# AUDIO_CODEC.net
KiCad netlist of a schematic drawn in Altium Designer
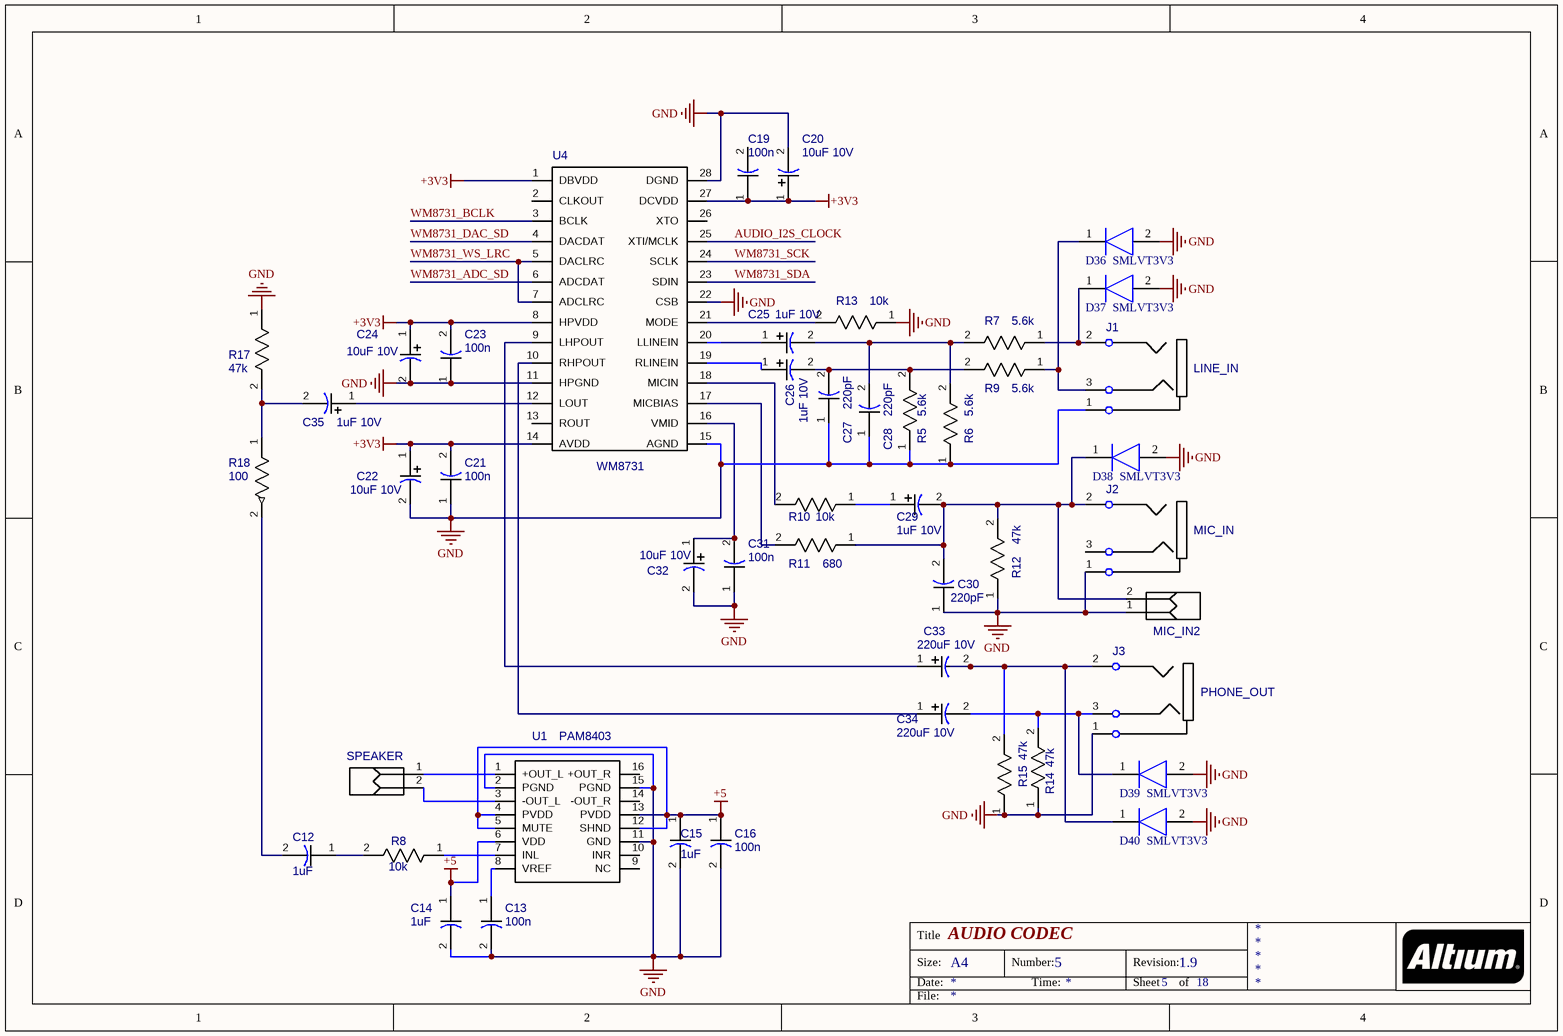
[diagram p0: AUDIO CODEC.SchDoc]

(export (version "E")
  (design (tool "Eeschema 10.0.6"))
  (components
    (comp (ref "C12")
      (value "1uF")
      (footprint "CAP_0805")
      (description "CAP_0805")
      (libsource (lib "*") (part "CAP_0805"))
    )
    (comp (ref "C13")
      (value "100n")
      (footprint "CAP_0805")
      (description "CAP_0805")
      (libsource (lib "*") (part "CAP_0805"))
    )
    (comp (ref "C14")
      (value "1uF")
      (footprint "CAP_0805")
      (description "CAP_0805")
      (libsource (lib "*") (part "CAP_0805"))
    )
    (comp (ref "C15")
      (value "1uF")
      (footprint "CAP_0805")
      (description "CAP_0805")
      (libsource (lib "*") (part "CAP_0805"))
    )
    (comp (ref "C16")
      (value "100n")
      (footprint "CAP_0805")
      (description "CAP_0805")
      (libsource (lib "*") (part "CAP_0805"))
    )
    (comp (ref "C19")
      (value "100n")
      (footprint "CAP_0805")
      (description "CAP_0805")
      (libsource (lib "*") (part "CAP_0805"))
    )
    (comp (ref "C20")
      (value "10uF 10V")
      (footprint "CAPAE_4.3x4.3h5.4")
      (description "CAPAE_4.3x4.3h5.4")
      (libsource (lib "*") (part "CAPAE_4.3x4.3h5.4"))
    )
    (comp (ref "C21")
      (value "100n")
      (footprint "CAP_0805")
      (description "CAP_0805")
      (libsource (lib "*") (part "CAP_0805"))
    )
    (comp (ref "C22")
      (value "10uF 10V")
      (footprint "CAPAE_4.3x4.3h5.4")
      (description "CAPAE_4.3x4.3h5.4")
      (libsource (lib "*") (part "CAPAE_4.3x4.3h5.4"))
    )
    (comp (ref "C23")
      (value "100n")
      (footprint "CAP_0805")
      (description "CAP_0805")
      (libsource (lib "*") (part "CAP_0805"))
    )
    (comp (ref "C24")
      (value "10uF 10V")
      (footprint "CAPAE_4.3x4.3h5.4")
      (description "CAPAE_4.3x4.3h5.4")
      (libsource (lib "*") (part "CAPAE_4.3x4.3h5.4"))
    )
    (comp (ref "C25")
      (value "1uF 10V")
      (footprint "CAPAE_4.3x4.3h5.4")
      (description "CAPAE_4.3x4.3h5.4")
      (libsource (lib "*") (part "CAPAE_4.3x4.3h5.4"))
    )
    (comp (ref "C26")
      (value "1uF 10V")
      (footprint "CAPAE_4.3x4.3h5.4")
      (description "CAPAE_4.3x4.3h5.4")
      (libsource (lib "*") (part "CAPAE_4.3x4.3h5.4"))
    )
    (comp (ref "C27")
      (value "220pF")
      (footprint "CAP_0805")
      (description "CAP_0805")
      (libsource (lib "*") (part "CAP_0805"))
    )
    (comp (ref "C28")
      (value "220pF")
      (footprint "CAP_0805")
      (description "CAP_0805")
      (libsource (lib "*") (part "CAP_0805"))
    )
    (comp (ref "C29")
      (value "1uF 10V")
      (footprint "CAPAE_4.3x4.3h5.4")
      (description "CAPAE_4.3x4.3h5.4")
      (libsource (lib "*") (part "CAPAE_4.3x4.3h5.4"))
    )
    (comp (ref "C30")
      (value "220pF")
      (footprint "CAP_0805")
      (description "CAP_0805")
      (libsource (lib "*") (part "CAP_0805"))
    )
    (comp (ref "C31")
      (value "100n")
      (footprint "CAP_0805")
      (description "CAP_0805")
      (libsource (lib "*") (part "CAP_0805"))
    )
    (comp (ref "C32")
      (value "10uF 10V")
      (footprint "CAPAE_4.3x4.3h5.4")
      (description "CAPAE_4.3x4.3h5.4")
      (libsource (lib "*") (part "CAPAE_4.3x4.3h5.4"))
    )
    (comp (ref "C33")
      (value "220uF 10V")
      (footprint "CAPAE_4.3x4.3h5.4")
      (description "CAPAE_4.3x4.3h5.4")
      (libsource (lib "*") (part "CAPAE_4.3x4.3h5.4"))
    )
    (comp (ref "C34")
      (value "220uF 10V")
      (footprint "CAPAE_4.3x4.3h5.4")
      (description "CAPAE_4.3x4.3h5.4")
      (libsource (lib "*") (part "CAPAE_4.3x4.3h5.4"))
    )
    (comp (ref "C35")
      (value "1uF 10V")
      (footprint "CAPAE_4.3x4.3h5.4")
      (description "CAPAE_4.3x4.3h5.4")
      (libsource (lib "*") (part "CAPAE_4.3x4.3h5.4"))
    )
    (comp (ref "D36")
      (value "SMLVT3V3")
      (footprint "SamacSys:SMBJ36CATR")
      (description "Diode")
      (fields (field (name "MOUSER PART NUMBER") "511-SMLVT3V3") (field (name "RS PART NUMBER") "5444821P"))
      (libsource (lib "*") (part "SMLVT3V3"))
    )
    (comp (ref "D37")
      (value "SMLVT3V3")
      (footprint "SamacSys:SMBJ36CATR")
      (description "Diode")
      (fields (field (name "MOUSER PART NUMBER") "511-SMLVT3V3") (field (name "RS PART NUMBER") "5444821P"))
      (libsource (lib "*") (part "SMLVT3V3"))
    )
    (comp (ref "D38")
      (value "SMLVT3V3")
      (footprint "SamacSys:SMBJ36CATR")
      (description "Diode")
      (fields (field (name "MOUSER PART NUMBER") "511-SMLVT3V3") (field (name "RS PART NUMBER") "5444821P"))
      (libsource (lib "*") (part "SMLVT3V3"))
    )
    (comp (ref "D39")
      (value "SMLVT3V3")
      (footprint "SamacSys:SMBJ36CATR")
      (description "Diode")
      (fields (field (name "MOUSER PART NUMBER") "511-SMLVT3V3") (field (name "RS PART NUMBER") "5444821P"))
      (libsource (lib "*") (part "SMLVT3V3"))
    )
    (comp (ref "D40")
      (value "SMLVT3V3")
      (footprint "SamacSys:SMBJ36CATR")
      (description "Diode")
      (fields (field (name "MOUSER PART NUMBER") "511-SMLVT3V3") (field (name "RS PART NUMBER") "5444821P"))
      (libsource (lib "*") (part "SMLVT3V3"))
    )
    (comp (ref "J1")
      (value "LINE_IN")
      (footprint "SJ1-3523N")
      (description "SJ1-3523N")
      (libsource (lib "*") (part "SJ1-3523N"))
    )
    (comp (ref "J2")
      (value "MIC_IN")
      (footprint "SJ1-3523N")
      (description "SJ1-3523N")
      (libsource (lib "*") (part "SJ1-3523N"))
    )
    (comp (ref "J3")
      (value "PHONE_OUT")
      (footprint "SJ1-3523N")
      (description "SJ1-3523N")
      (libsource (lib "*") (part "SJ1-3523N"))
    )
    (comp (ref "MIС_IN2")
      (value "MIС_IN2")
      (footprint "51022-0200")
      (description "2 Pin")
      (libsource (lib "*") (part "51022-0200"))
    )
    (comp (ref "R5")
      (value "5.6k")
      (footprint "RES_0805")
      (description "RES_0805")
      (libsource (lib "*") (part "RES_0805"))
    )
    (comp (ref "R6")
      (value "5.6k")
      (footprint "RES_0805")
      (description "RES_0805")
      (libsource (lib "*") (part "RES_0805"))
    )
    (comp (ref "R7")
      (value "5.6k")
      (footprint "RES_0805")
      (description "RES_0805")
      (libsource (lib "*") (part "RES_0805"))
    )
    (comp (ref "R8")
      (value "10k")
      (footprint "RES_0805")
      (description "RES_0805")
      (libsource (lib "*") (part "RES_0805"))
    )
    (comp (ref "R9")
      (value "5.6k")
      (footprint "RES_0805")
      (description "RES_0805")
      (libsource (lib "*") (part "RES_0805"))
    )
    (comp (ref "R10")
      (value "10k")
      (footprint "RES_0805")
      (description "RES_0805")
      (libsource (lib "*") (part "RES_0805"))
    )
    (comp (ref "R11")
      (value "680")
      (footprint "RES_0805")
      (description "RES_0805")
      (libsource (lib "*") (part "RES_0805"))
    )
    (comp (ref "R12")
      (value "47k")
      (footprint "RES_0805")
      (description "RES_0805")
      (libsource (lib "*") (part "RES_0805"))
    )
    (comp (ref "R13")
      (value "10k")
      (footprint "RES_0805")
      (description "RES_0805")
      (libsource (lib "*") (part "RES_0805"))
    )
    (comp (ref "R14")
      (value "47k")
      (footprint "RES_0805")
      (description "RES_0805")
      (libsource (lib "*") (part "RES_0805"))
    )
    (comp (ref "R15")
      (value "47k")
      (footprint "RES_0805")
      (description "RES_0805")
      (libsource (lib "*") (part "RES_0805"))
    )
    (comp (ref "R17")
      (value "47k")
      (footprint "RES_0805")
      (description "RES_0805")
      (libsource (lib "*") (part "RES_0805"))
    )
    (comp (ref "R18")
      (value "100")
      (footprint "RES_0805")
      (description "RES_0805")
      (libsource (lib "*") (part "RES_0805"))
    )
    (comp (ref "SPEAKER")
      (value "~")
      (footprint "51022-0200")
      (description "51022-0200")
      (libsource (lib "*") (part "51022-0200"))
    )
    (comp (ref "U1") (value "PAM8403") (footprint "PAM8403") (libsource (lib "*") (part "PAM8403")))
    (comp (ref "U4") (value "WM8731") (footprint "WM8731") (libsource (lib "*") (part "WM8731")))
  )
  (nets
    (net (code "1") (name "+3V3") (class "Default")
      (node (ref "C19") (pin "1") (pinfunction "1_1") (pintype "passive"))
      (node (ref "C20") (pin "1") (pinfunction "PLUS_1") (pintype "passive"))
      (node (ref "C21") (pin "2") (pinfunction "2_2") (pintype "passive"))
      (node (ref "C22") (pin "1") (pinfunction "PLUS_1") (pintype "passive"))
      (node (ref "C23") (pin "2") (pinfunction "2_2") (pintype "passive"))
      (node (ref "C24") (pin "1") (pinfunction "PLUS_1") (pintype "passive"))
      (node (ref "U4") (pin "1") (pinfunction "DBVDD_1") (pintype "passive"))
      (node (ref "U4") (pin "14") (pinfunction "AVDD_14") (pintype "passive"))
      (node (ref "U4") (pin "27") (pinfunction "DCVDD_27") (pintype "passive"))
      (node (ref "U4") (pin "8") (pinfunction "HPVDD_8") (pintype "passive"))
    )
    (net (code "2") (name "+5") (class "Default")
      (node (ref "C14") (pin "1") (pinfunction "1_1") (pintype "passive"))
      (node (ref "C15") (pin "1") (pinfunction "1_1") (pintype "passive"))
      (node (ref "C16") (pin "1") (pinfunction "1_1") (pintype "passive"))
      (node (ref "U1") (pin "12") (pinfunction "SHND_12") (pintype "passive"))
      (node (ref "U1") (pin "13") (pinfunction "PVDD_13") (pintype "passive"))
      (node (ref "U1") (pin "4") (pinfunction "PVDD_4") (pintype "passive"))
      (node (ref "U1") (pin "5") (pinfunction "MUTE_5") (pintype "passive"))
      (node (ref "U1") (pin "6") (pinfunction "VDD_6") (pintype "passive"))
    )
    (net (code "3") (name "/AUDIO_I2S_CLOCK") (class "Default")
      (node (ref "U4") (pin "25") (pinfunction "XTI/MCLK_25") (pintype "passive"))
    )
    (net (code "4") (name "/WM8731_ADC_SD") (class "Default")
      (node (ref "U4") (pin "6") (pinfunction "ADCDAT_6") (pintype "passive"))
    )
    (net (code "5") (name "/WM8731_BCLK") (class "Default")
      (node (ref "U4") (pin "3") (pinfunction "BCLK_3") (pintype "passive"))
    )
    (net (code "6") (name "/WM8731_DAC_SD") (class "Default")
      (node (ref "U4") (pin "4") (pinfunction "DACDAT_4") (pintype "passive"))
    )
    (net (code "7") (name "/WM8731_SCK") (class "Default")
      (node (ref "U4") (pin "24") (pinfunction "SCLK_24") (pintype "passive"))
    )
    (net (code "8") (name "/WM8731_SDA") (class "Default")
      (node (ref "U4") (pin "23") (pinfunction "SDIN_23") (pintype "passive"))
    )
    (net (code "9") (name "/WM8731_WS_LRC") (class "Default")
      (node (ref "U4") (pin "5") (pinfunction "DACLRC_5") (pintype "passive"))
      (node (ref "U4") (pin "7") (pinfunction "ADCLRC_7") (pintype "passive"))
    )
    (net (code "10") (name "GND") (class "Default")
      (node (ref "C13") (pin "2") (pinfunction "2_2") (pintype "passive"))
      (node (ref "C14") (pin "2") (pinfunction "2_2") (pintype "passive"))
      (node (ref "C15") (pin "2") (pinfunction "2_2") (pintype "passive"))
      (node (ref "C16") (pin "2") (pinfunction "2_2") (pintype "passive"))
      (node (ref "C20") (pin "2") (pinfunction "MINUS_2") (pintype "passive"))
      (node (ref "C21") (pin "1") (pinfunction "1_1") (pintype "passive"))
      (node (ref "C22") (pin "2") (pinfunction "MINUS_2") (pintype "passive"))
      (node (ref "C23") (pin "1") (pinfunction "1_1") (pintype "passive"))
      (node (ref "C24") (pin "2") (pinfunction "MINUS_2") (pintype "passive"))
      (node (ref "C27") (pin "1") (pinfunction "1_1") (pintype "passive"))
      (node (ref "C28") (pin "1") (pinfunction "1_1") (pintype "passive"))
      (node (ref "C30") (pin "1") (pinfunction "1_1") (pintype "passive"))
      (node (ref "C31") (pin "1") (pinfunction "1_1") (pintype "passive"))
      (node (ref "C32") (pin "2") (pinfunction "MINUS_2") (pintype "passive"))
      (node (ref "D36") (pin "2") (pinfunction "A_2") (pintype "passive"))
      (node (ref "D37") (pin "2") (pinfunction "A_2") (pintype "passive"))
      (node (ref "D38") (pin "2") (pinfunction "A_2") (pintype "passive"))
      (node (ref "D39") (pin "2") (pinfunction "A_2") (pintype "passive"))
      (node (ref "D40") (pin "2") (pinfunction "A_2") (pintype "passive"))
      (node (ref "J1") (pin "1") (pinfunction "sleeve_1") (pintype "passive"))
      (node (ref "J2") (pin "1") (pinfunction "sleeve_1") (pintype "passive"))
      (node (ref "J3") (pin "1") (pinfunction "sleeve_1") (pintype "passive"))
      (node (ref "MIС_IN2") (pin "1") (pinfunction "1_1") (pintype "passive"))
      (node (ref "R12") (pin "1") (pinfunction "1_1") (pintype "passive"))
      (node (ref "R13") (pin "1") (pinfunction "1_1") (pintype "passive"))
      (node (ref "R14") (pin "1") (pinfunction "1_1") (pintype "passive"))
      (node (ref "R15") (pin "1") (pinfunction "1_1") (pintype "passive"))
      (node (ref "R17") (pin "1") (pinfunction "1_1") (pintype "passive"))
      (node (ref "R5") (pin "1") (pinfunction "1_1") (pintype "passive"))
      (node (ref "R6") (pin "1") (pinfunction "1_1") (pintype "passive"))
      (node (ref "U1") (pin "11") (pinfunction "GND_11") (pintype "passive"))
      (node (ref "U1") (pin "15") (pinfunction "PGND_15") (pintype "passive"))
      (node (ref "U1") (pin "2") (pinfunction "PGND_2") (pintype "passive"))
      (node (ref "U4") (pin "11") (pinfunction "HPGND_11") (pintype "passive"))
      (node (ref "U4") (pin "15") (pinfunction "AGND_15") (pintype "passive"))
      (node (ref "U4") (pin "22") (pinfunction "CSB_22") (pintype "passive"))
      (node (ref "U4") (pin "28") (pinfunction "DGND_28") (pintype "passive"))
    )
    (net (code "11") (name "Net-(C12-Pad1)") (class "Default")
      (node (ref "C12") (pin "1") (pinfunction "1_1") (pintype "passive"))
      (node (ref "R8") (pin "2") (pinfunction "2_2") (pintype "output"))
    )
    (net (code "12") (name "Net-(C12-Pad2)") (class "Default")
      (node (ref "C12") (pin "2") (pinfunction "2_2") (pintype "passive"))
      (node (ref "R18") (pin "2") (pinfunction "2_2") (pintype "output"))
    )
    (net (code "13") (name "Net-(C25-MINUS)") (class "Default")
      (node (ref "C25") (pin "2") (pinfunction "MINUS_2") (pintype "passive"))
      (node (ref "C28") (pin "2") (pinfunction "2_2") (pintype "passive"))
      (node (ref "R6") (pin "2") (pinfunction "2_2") (pintype "output"))
      (node (ref "R7") (pin "2") (pinfunction "2_2") (pintype "output"))
    )
    (net (code "14") (name "Net-(C25-PLUS)") (class "Default")
      (node (ref "C25") (pin "1") (pinfunction "PLUS_1") (pintype "passive"))
      (node (ref "U4") (pin "20") (pinfunction "LLINEIN_20") (pintype "passive"))
    )
    (net (code "15") (name "Net-(C26-MINUS)") (class "Default")
      (node (ref "C26") (pin "2") (pinfunction "MINUS_2") (pintype "passive"))
      (node (ref "C27") (pin "2") (pinfunction "2_2") (pintype "passive"))
      (node (ref "R5") (pin "2") (pinfunction "2_2") (pintype "output"))
      (node (ref "R9") (pin "2") (pinfunction "2_2") (pintype "output"))
    )
    (net (code "16") (name "Net-(C26-PLUS)") (class "Default")
      (node (ref "C26") (pin "1") (pinfunction "PLUS_1") (pintype "passive"))
      (node (ref "U4") (pin "19") (pinfunction "RLINEIN_19") (pintype "passive"))
    )
    (net (code "17") (name "Net-(C29-MINUS)") (class "Default")
      (node (ref "C29") (pin "2") (pinfunction "MINUS_2") (pintype "passive"))
      (node (ref "C30") (pin "2") (pinfunction "2_2") (pintype "passive"))
      (node (ref "D38") (pin "1") (pinfunction "K_1") (pintype "passive"))
      (node (ref "J2") (pin "2") (pinfunction "tip_2") (pintype "passive"))
      (node (ref "MIС_IN2") (pin "2") (pinfunction "2_2") (pintype "passive"))
      (node (ref "R11") (pin "1") (pinfunction "1_1") (pintype "passive"))
      (node (ref "R12") (pin "2") (pinfunction "2_2") (pintype "output"))
    )
    (net (code "18") (name "Net-(C29-PLUS)") (class "Default")
      (node (ref "C29") (pin "1") (pinfunction "PLUS_1") (pintype "passive"))
      (node (ref "R10") (pin "1") (pinfunction "1_1") (pintype "passive"))
    )
    (net (code "19") (name "Net-(C32-PLUS)") (class "Default")
      (node (ref "C31") (pin "2") (pinfunction "2_2") (pintype "passive"))
      (node (ref "C32") (pin "1") (pinfunction "PLUS_1") (pintype "passive"))
      (node (ref "U4") (pin "16") (pinfunction "VMID_16") (pintype "passive"))
    )
    (net (code "20") (name "Net-(C33-MINUS)") (class "Default")
      (node (ref "C33") (pin "2") (pinfunction "MINUS_2") (pintype "passive"))
      (node (ref "D40") (pin "1") (pinfunction "K_1") (pintype "passive"))
      (node (ref "J3") (pin "2") (pinfunction "tip_2") (pintype "passive"))
      (node (ref "R15") (pin "2") (pinfunction "2_2") (pintype "output"))
    )
    (net (code "21") (name "Net-(C33-PLUS)") (class "Default")
      (node (ref "C33") (pin "1") (pinfunction "PLUS_1") (pintype "passive"))
      (node (ref "U4") (pin "9") (pinfunction "LHPOUT_9") (pintype "passive"))
    )
    (net (code "22") (name "Net-(C34-MINUS)") (class "Default")
      (node (ref "C34") (pin "2") (pinfunction "MINUS_2") (pintype "passive"))
      (node (ref "D39") (pin "1") (pinfunction "K_1") (pintype "passive"))
      (node (ref "J3") (pin "3") (pinfunction "ring_3") (pintype "passive"))
      (node (ref "R14") (pin "2") (pinfunction "2_2") (pintype "output"))
    )
    (net (code "23") (name "Net-(C34-PLUS)") (class "Default")
      (node (ref "C34") (pin "1") (pinfunction "PLUS_1") (pintype "passive"))
      (node (ref "U4") (pin "10") (pinfunction "RHPOUT_10") (pintype "passive"))
    )
    (net (code "24") (name "Net-(C35-MINUS)") (class "Default")
      (node (ref "C35") (pin "2") (pinfunction "MINUS_2") (pintype "passive"))
      (node (ref "R17") (pin "2") (pinfunction "2_2") (pintype "output"))
      (node (ref "R18") (pin "1") (pinfunction "1_1") (pintype "passive"))
    )
    (net (code "25") (name "Net-(C35-PLUS)") (class "Default")
      (node (ref "C35") (pin "1") (pinfunction "PLUS_1") (pintype "passive"))
      (node (ref "U4") (pin "12") (pinfunction "LOUT_12") (pintype "passive"))
    )
    (net (code "26") (name "Net-(D36-K)") (class "Default")
      (node (ref "D36") (pin "1") (pinfunction "K_1") (pintype "passive"))
      (node (ref "J1") (pin "3") (pinfunction "ring_3") (pintype "passive"))
      (node (ref "R9") (pin "1") (pinfunction "1_1") (pintype "passive"))
    )
    (net (code "27") (name "Net-(D37-K)") (class "Default")
      (node (ref "D37") (pin "1") (pinfunction "K_1") (pintype "passive"))
      (node (ref "J1") (pin "2") (pinfunction "tip_2") (pintype "passive"))
      (node (ref "R7") (pin "1") (pinfunction "1_1") (pintype "passive"))
    )
    (net (code "28") (name "Net-(U1-+OUT_L)") (class "Default")
      (node (ref "SPEAKER") (pin "1") (pinfunction "1_1") (pintype "passive"))
      (node (ref "U1") (pin "1") (pinfunction "+OUT_L_1") (pintype "passive"))
    )
    (net (code "29") (name "Net-(U1--OUT_L)") (class "Default")
      (node (ref "SPEAKER") (pin "2") (pinfunction "2_2") (pintype "passive"))
      (node (ref "U1") (pin "3") (pinfunction "-OUT_L_3") (pintype "passive"))
    )
    (net (code "30") (name "Net-(U1-INL)") (class "Default")
      (node (ref "R8") (pin "1") (pinfunction "1_1") (pintype "passive"))
      (node (ref "U1") (pin "7") (pinfunction "INL_7") (pintype "passive"))
    )
    (net (code "31") (name "Net-(U1-VREF)") (class "Default")
      (node (ref "C13") (pin "1") (pinfunction "1_1") (pintype "passive"))
      (node (ref "U1") (pin "8") (pinfunction "VREF_8") (pintype "passive"))
    )
    (net (code "32") (name "Net-(U4-MICBIAS)") (class "Default")
      (node (ref "R11") (pin "2") (pinfunction "2_2") (pintype "output"))
      (node (ref "U4") (pin "17") (pinfunction "MICBIAS_17") (pintype "passive"))
    )
    (net (code "33") (name "Net-(U4-MICIN)") (class "Default")
      (node (ref "R10") (pin "2") (pinfunction "2_2") (pintype "output"))
      (node (ref "U4") (pin "18") (pinfunction "MICIN_18") (pintype "passive"))
    )
    (net (code "34") (name "Net-(U4-MODE)") (class "Default")
      (node (ref "R13") (pin "2") (pinfunction "2_2") (pintype "output"))
      (node (ref "U4") (pin "21") (pinfunction "MODE_21") (pintype "passive"))
    )
    (net (code "35") (name "unconnected-(C19-Pad2)") (class "Default")
      (node (ref "C19") (pin "2") (pinfunction "2_2") (pintype "passive"))
    )
    (net (code "36") (name "unconnected-(J2-ring-Pad3)") (class "Default")
      (node (ref "J2") (pin "3") (pinfunction "ring_3") (pintype "passive"))
    )
    (net (code "37") (name "unconnected-(U1-+OUT_R-Pad16)") (class "Default")
      (node (ref "U1") (pin "16") (pinfunction "+OUT_R_16") (pintype "passive"))
    )
    (net (code "38") (name "unconnected-(U1--OUT_R-Pad14)") (class "Default")
      (node (ref "U1") (pin "14") (pinfunction "-OUT_R_14") (pintype "passive"))
    )
    (net (code "39") (name "unconnected-(U1-INR-Pad10)") (class "Default")
      (node (ref "U1") (pin "10") (pinfunction "INR_10") (pintype "passive"))
    )
    (net (code "40") (name "unconnected-(U1-NC-Pad9)") (class "Default")
      (node (ref "U1") (pin "9") (pinfunction "NC_9") (pintype "passive"))
    )
    (net (code "41") (name "unconnected-(U4-CLKOUT-Pad2)") (class "Default")
      (node (ref "U4") (pin "2") (pinfunction "CLKOUT_2") (pintype "passive"))
    )
    (net (code "42") (name "unconnected-(U4-ROUT-Pad13)") (class "Default")
      (node (ref "U4") (pin "13") (pinfunction "ROUT_13") (pintype "passive"))
    )
    (net (code "43") (name "unconnected-(U4-XTO-Pad26)") (class "Default")
      (node (ref "U4") (pin "26") (pinfunction "XTO_26") (pintype "passive"))
    )
  )
)
